# Main_Schematic.net
KiCad netlist of a schematic drawn in Altium Designer
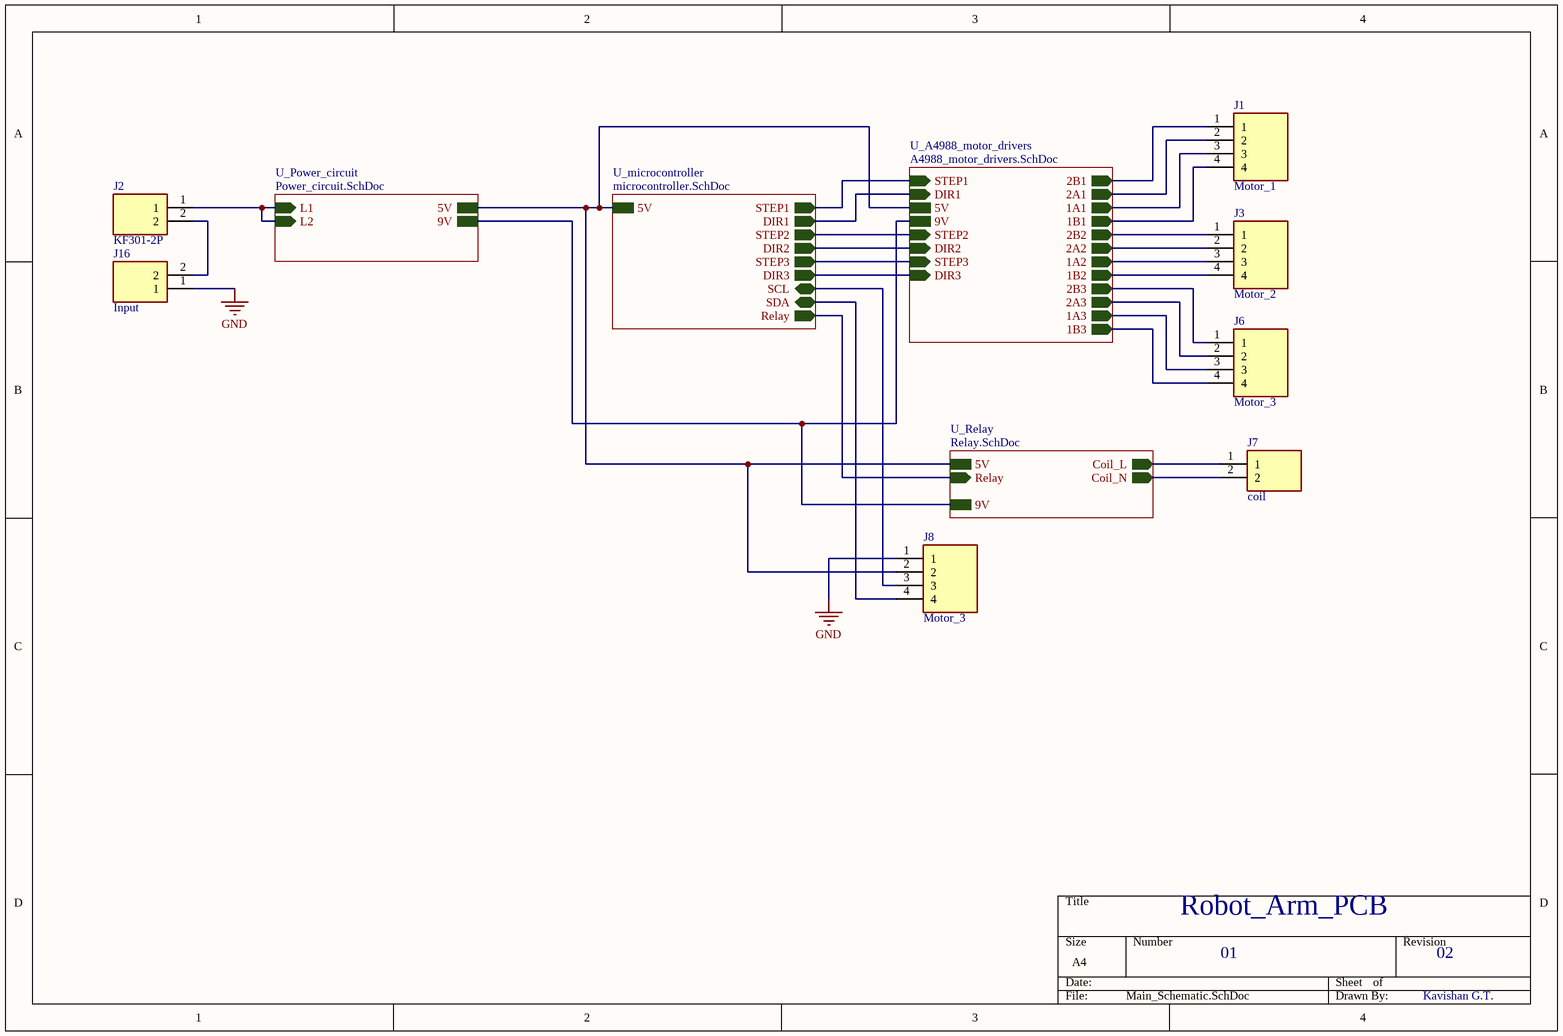
[diagram p0: Main_Schematic.SchDoc]

(export (version "E")
  (design (tool "Eeschema 10.0.6"))
  (components
    (comp (ref "J1")
      (value "Motor_1")
      (footprint "SamacSys:SHDRRA4W64P0X250_1X4_1240X1150X700P")
      (description "Connector")
      (fields (field (name "MANUFACTURER_PART_NUMBER") "S4B-XH-A(LF)(SN)"))
      (libsource (lib "*") (part "S4B-XH-A_LF__SN_"))
    )
    (comp (ref "J2")
      (value "KF301-2P")
      (footprint "SamacSys:KF3012P")
      (description "Connector")
      (libsource (lib "*") (part "KF301-2P"))
    )
    (comp (ref "J3")
      (value "Motor_2")
      (footprint "SamacSys:SHDRRA4W64P0X250_1X4_1240X1150X700P")
      (description "Connector")
      (fields (field (name "MANUFACTURER_PART_NUMBER") "S4B-XH-A(LF)(SN)"))
      (libsource (lib "*") (part "S4B-XH-A_LF__SN_"))
    )
    (comp (ref "J6")
      (value "Motor_3")
      (footprint "SamacSys:SHDRRA4W64P0X250_1X4_1240X1150X700P")
      (description "Connector")
      (fields (field (name "MANUFACTURER_PART_NUMBER") "S4B-XH-A(LF)(SN)"))
      (libsource (lib "*") (part "S4B-XH-A_LF__SN_"))
    )
    (comp (ref "J7")
      (value "coil")
      (footprint "SamacSys:SHDR2W64P0X250_1X2_750X380X600P")
      (description "Connector")
      (fields (field (name "MANUFACTURER_PART_NUMBER") "B2B-EH-A"))
      (libsource (lib "") (part "B2B-EH-A_1"))
    )
    (comp (ref "J8")
      (value "Motor_3")
      (footprint "SamacSys:SHDRRA4W64P0X250_1X4_1240X1150X700P")
      (description "Connector")
      (fields (field (name "MANUFACTURER_PART_NUMBER") "S4B-XH-A(LF)(SN)"))
      (libsource (lib "*") (part "S4B-XH-A_LF__SN_"))
    )
    (comp (ref "J16")
      (value "Input")
      (footprint "SamacSys:SHDR2W64P0X250_1X2_750X380X600P")
      (description "Connector")
      (fields (field (name "MANUFACTURER_PART_NUMBER") "B2B-EH-A"))
      (libsource (lib "*") (part "B2B-EH-A"))
    )
  )
  (nets
    (net (code "1") (name "/1A1") (class "Default")
      (node (ref "J1") (pin "3") (pinfunction "3_3") (pintype "passive"))
    )
    (net (code "2") (name "/1A2") (class "Default")
      (node (ref "J3") (pin "3") (pinfunction "3_3") (pintype "passive"))
    )
    (net (code "3") (name "/1A3") (class "Default")
      (node (ref "J6") (pin "3") (pinfunction "3_3") (pintype "passive"))
    )
    (net (code "4") (name "/1B1") (class "Default")
      (node (ref "J1") (pin "4") (pinfunction "4_4") (pintype "passive"))
    )
    (net (code "5") (name "/1B2") (class "Default")
      (node (ref "J3") (pin "4") (pinfunction "4_4") (pintype "passive"))
    )
    (net (code "6") (name "/1B3") (class "Default")
      (node (ref "J6") (pin "4") (pinfunction "4_4") (pintype "passive"))
    )
    (net (code "7") (name "/2A1") (class "Default")
      (node (ref "J1") (pin "2") (pinfunction "2_2") (pintype "passive"))
    )
    (net (code "8") (name "/2A2") (class "Default")
      (node (ref "J3") (pin "2") (pinfunction "2_2") (pintype "passive"))
    )
    (net (code "9") (name "/2A3") (class "Default")
      (node (ref "J6") (pin "2") (pinfunction "2_2") (pintype "passive"))
    )
    (net (code "10") (name "/2B1") (class "Default")
      (node (ref "J1") (pin "1") (pinfunction "1_1") (pintype "passive"))
    )
    (net (code "11") (name "/2B2") (class "Default")
      (node (ref "J3") (pin "1") (pinfunction "1_1") (pintype "passive"))
    )
    (net (code "12") (name "/2B3") (class "Default")
      (node (ref "J6") (pin "1") (pinfunction "1_1") (pintype "passive"))
    )
    (net (code "13") (name "/5V") (class "Default")
      (node (ref "J8") (pin "2") (pinfunction "2_2") (pintype "passive"))
    )
    (net (code "15") (name "/Coil_L") (class "Default")
      (node (ref "J7") (pin "1") (pinfunction "1_1") (pintype "passive"))
    )
    (net (code "16") (name "/Coil_N") (class "Default")
      (node (ref "J7") (pin "2") (pinfunction "2_2") (pintype "passive"))
    )
    (net (code "20") (name "/L1") (class "Default")
      (node (ref "J2") (pin "1") (pinfunction "1_1") (pintype "passive"))
    )
    (net (code "22") (name "/SCL") (class "Default")
      (node (ref "J8") (pin "3") (pinfunction "3_3") (pintype "passive"))
    )
    (net (code "23") (name "/SDA") (class "Default")
      (node (ref "J8") (pin "4") (pinfunction "4_4") (pintype "passive"))
    )
    (net (code "27") (name "GND") (class "Default")
      (node (ref "J16") (pin "1") (pinfunction "1_1") (pintype "passive"))
      (node (ref "J8") (pin "1") (pinfunction "1_1") (pintype "passive"))
    )
    (net (code "28") (name "Net-(J16-Pad2)") (class "Default")
      (node (ref "J16") (pin "2") (pinfunction "2_2") (pintype "passive"))
      (node (ref "J2") (pin "2") (pinfunction "2_2") (pintype "passive"))
    )
  )
)
